# 07_FPGA_banks_1_2_3_4.net
KiCad netlist of a schematic drawn in Altium Designer
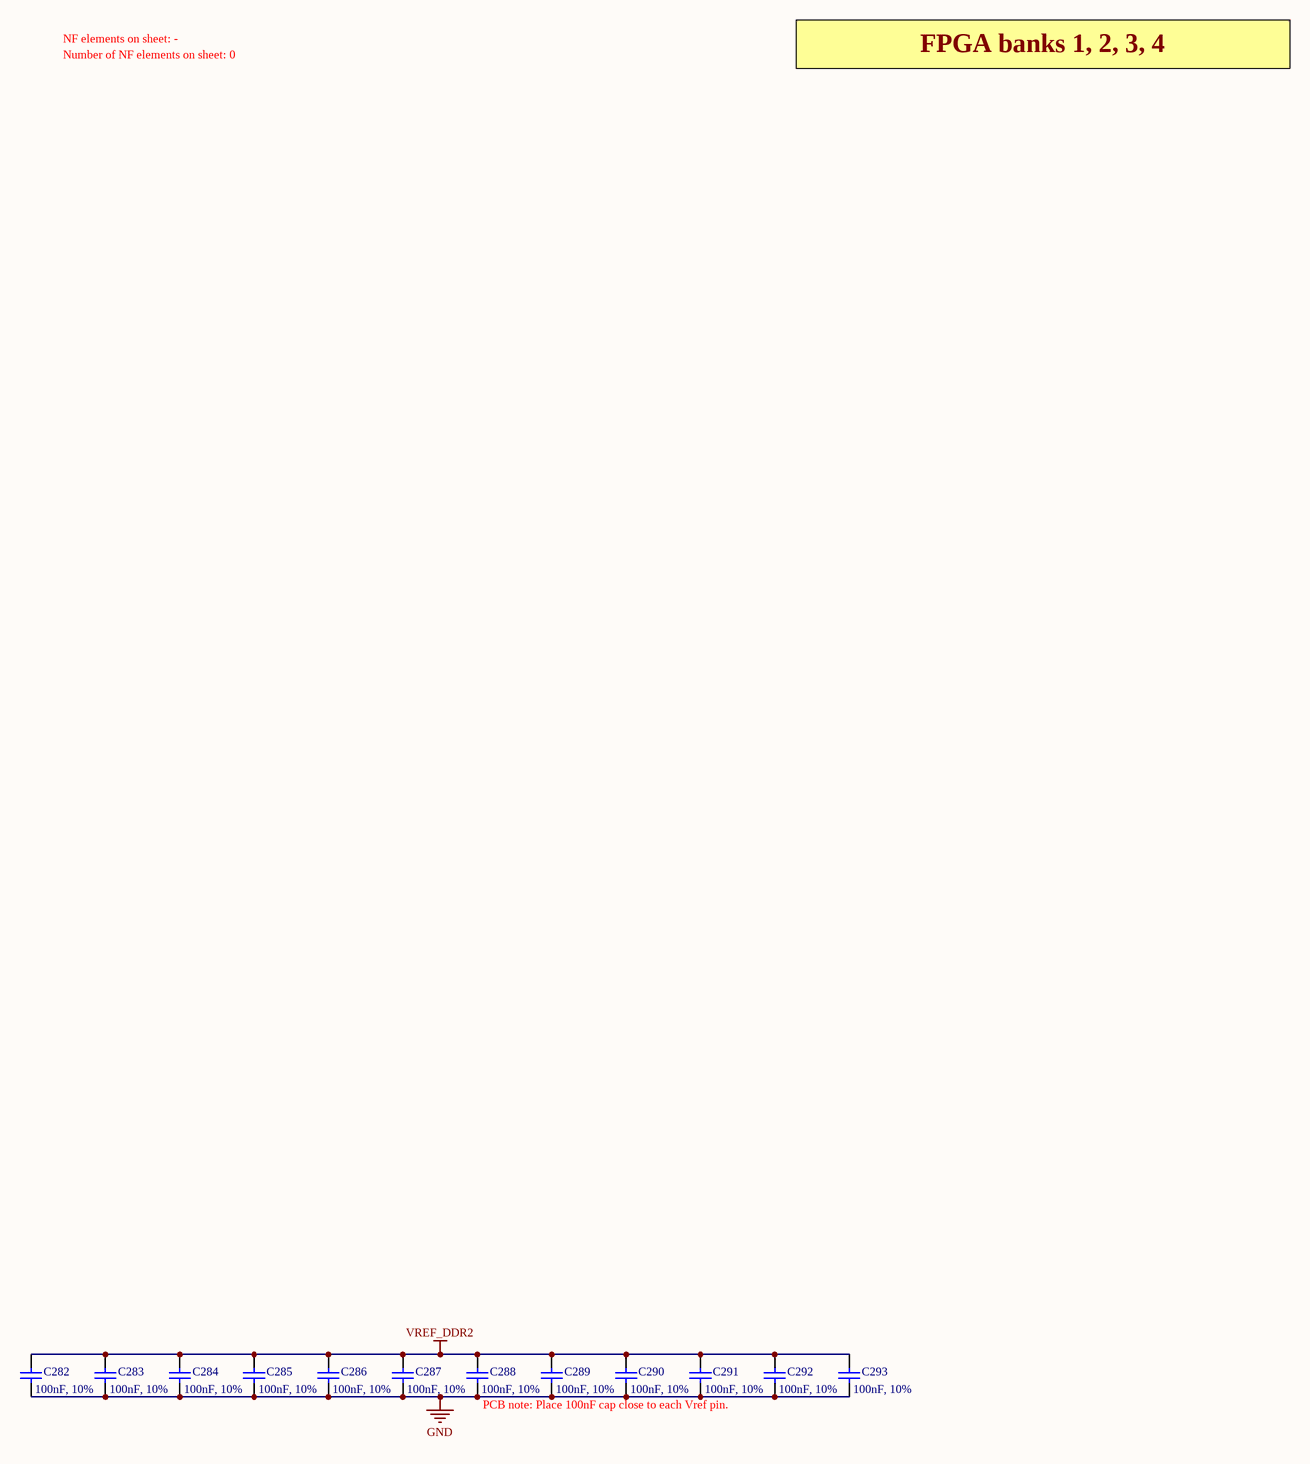
[diagram p0: 07_FPGA_banks_1_2_3_4.SchDoc]

(export (version "E")
  (design (tool "Eeschema 10.0.6"))
  (components
    (comp (ref "C282")
      (value "100nF, 10%")
      (footprint "CAP0402")
      (fields
        (field (name "TOLERANCE") "10 %")
        (field (name "MANUFACTURER") "Murata Electronics")
        (field (name "MANUFACTURER PART NUMBER") "GRM155R71C104KA88D")
      )
      (libsource (lib "LimeFPGAboard_schLib") (part "Cap_0603"))
    )
    (comp (ref "C283")
      (value "100nF, 10%")
      (footprint "CAP0402")
      (fields
        (field (name "TOLERANCE") "10 %")
        (field (name "MANUFACTURER") "Murata Electronics")
        (field (name "MANUFACTURER PART NUMBER") "GRM155R71C104KA88D")
      )
      (libsource (lib "LimeFPGAboard_schLib") (part "Cap_0603"))
    )
    (comp (ref "C284")
      (value "100nF, 10%")
      (footprint "CAP0402")
      (fields
        (field (name "TOLERANCE") "10 %")
        (field (name "MANUFACTURER") "Murata Electronics")
        (field (name "MANUFACTURER PART NUMBER") "GRM155R71C104KA88D")
      )
      (libsource (lib "LimeFPGAboard_schLib") (part "Cap_0603"))
    )
    (comp (ref "C285")
      (value "100nF, 10%")
      (footprint "CAP0402")
      (fields
        (field (name "TOLERANCE") "10 %")
        (field (name "MANUFACTURER") "Murata Electronics")
        (field (name "MANUFACTURER PART NUMBER") "GRM155R71C104KA88D")
      )
      (libsource (lib "LimeFPGAboard_schLib") (part "Cap_0603"))
    )
    (comp (ref "C286")
      (value "100nF, 10%")
      (footprint "CAP0402")
      (fields
        (field (name "TOLERANCE") "10 %")
        (field (name "MANUFACTURER") "Murata Electronics")
        (field (name "MANUFACTURER PART NUMBER") "GRM155R71C104KA88D")
      )
      (libsource (lib "LimeFPGAboard_schLib") (part "Cap_0603"))
    )
    (comp (ref "C287")
      (value "100nF, 10%")
      (footprint "CAP0402")
      (fields
        (field (name "TOLERANCE") "10 %")
        (field (name "MANUFACTURER") "Murata Electronics")
        (field (name "MANUFACTURER PART NUMBER") "GRM155R71C104KA88D")
      )
      (libsource (lib "LimeFPGAboard_schLib") (part "Cap_0603"))
    )
    (comp (ref "C288")
      (value "100nF, 10%")
      (footprint "CAP0402")
      (fields
        (field (name "TOLERANCE") "10 %")
        (field (name "MANUFACTURER") "Murata Electronics")
        (field (name "MANUFACTURER PART NUMBER") "GRM155R71C104KA88D")
      )
      (libsource (lib "LimeFPGAboard_schLib") (part "Cap_0603"))
    )
    (comp (ref "C289")
      (value "100nF, 10%")
      (footprint "CAP0402")
      (fields
        (field (name "TOLERANCE") "10 %")
        (field (name "MANUFACTURER") "Murata Electronics")
        (field (name "MANUFACTURER PART NUMBER") "GRM155R71C104KA88D")
      )
      (libsource (lib "LimeFPGAboard_schLib") (part "Cap_0603"))
    )
    (comp (ref "C290")
      (value "100nF, 10%")
      (footprint "CAP0402")
      (fields
        (field (name "TOLERANCE") "10 %")
        (field (name "MANUFACTURER") "Murata Electronics")
        (field (name "MANUFACTURER PART NUMBER") "GRM155R71C104KA88D")
      )
      (libsource (lib "LimeFPGAboard_schLib") (part "Cap_0603"))
    )
    (comp (ref "C291")
      (value "100nF, 10%")
      (footprint "CAP0402")
      (fields
        (field (name "TOLERANCE") "10 %")
        (field (name "MANUFACTURER") "Murata Electronics")
        (field (name "MANUFACTURER PART NUMBER") "GRM155R71C104KA88D")
      )
      (libsource (lib "LimeFPGAboard_schLib") (part "Cap_0603"))
    )
    (comp (ref "C292")
      (value "100nF, 10%")
      (footprint "CAP0402")
      (fields
        (field (name "TOLERANCE") "10 %")
        (field (name "MANUFACTURER") "Murata Electronics")
        (field (name "MANUFACTURER PART NUMBER") "GRM155R71C104KA88D")
      )
      (libsource (lib "LimeFPGAboard_schLib") (part "Cap_0603"))
    )
    (comp (ref "C293")
      (value "100nF, 10%")
      (footprint "CAP0402")
      (fields
        (field (name "TOLERANCE") "10 %")
        (field (name "MANUFACTURER") "Murata Electronics")
        (field (name "MANUFACTURER PART NUMBER") "GRM155R71C104KA88D")
      )
      (libsource (lib "LimeFPGAboard_schLib") (part "Cap_0603"))
    )
  )
  (nets
    (net (code "1") (name "GND") (class "Default")
      (node (ref "C282") (pin "2") (pinfunction "2_2") (pintype "passive"))
      (node (ref "C283") (pin "2") (pinfunction "2_2") (pintype "passive"))
      (node (ref "C284") (pin "2") (pinfunction "2_2") (pintype "passive"))
      (node (ref "C285") (pin "2") (pinfunction "2_2") (pintype "passive"))
      (node (ref "C286") (pin "2") (pinfunction "2_2") (pintype "passive"))
      (node (ref "C287") (pin "2") (pinfunction "2_2") (pintype "passive"))
      (node (ref "C288") (pin "2") (pinfunction "2_2") (pintype "passive"))
      (node (ref "C289") (pin "2") (pinfunction "2_2") (pintype "passive"))
      (node (ref "C290") (pin "2") (pinfunction "2_2") (pintype "passive"))
      (node (ref "C291") (pin "2") (pinfunction "2_2") (pintype "passive"))
      (node (ref "C292") (pin "2") (pinfunction "2_2") (pintype "passive"))
      (node (ref "C293") (pin "2") (pinfunction "2_2") (pintype "passive"))
    )
    (net (code "2") (name "VREF_DDR2") (class "Default")
      (node (ref "C282") (pin "1") (pinfunction "1_1") (pintype "passive"))
      (node (ref "C283") (pin "1") (pinfunction "1_1") (pintype "passive"))
      (node (ref "C284") (pin "1") (pinfunction "1_1") (pintype "passive"))
      (node (ref "C285") (pin "1") (pinfunction "1_1") (pintype "passive"))
      (node (ref "C286") (pin "1") (pinfunction "1_1") (pintype "passive"))
      (node (ref "C287") (pin "1") (pinfunction "1_1") (pintype "passive"))
      (node (ref "C288") (pin "1") (pinfunction "1_1") (pintype "passive"))
      (node (ref "C289") (pin "1") (pinfunction "1_1") (pintype "passive"))
      (node (ref "C290") (pin "1") (pinfunction "1_1") (pintype "passive"))
      (node (ref "C291") (pin "1") (pinfunction "1_1") (pintype "passive"))
      (node (ref "C292") (pin "1") (pinfunction "1_1") (pintype "passive"))
      (node (ref "C293") (pin "1") (pinfunction "1_1") (pintype "passive"))
    )
  )
)
